# EFR32BG24_PartB.net
KiCad netlist of a schematic drawn in Altium Designer
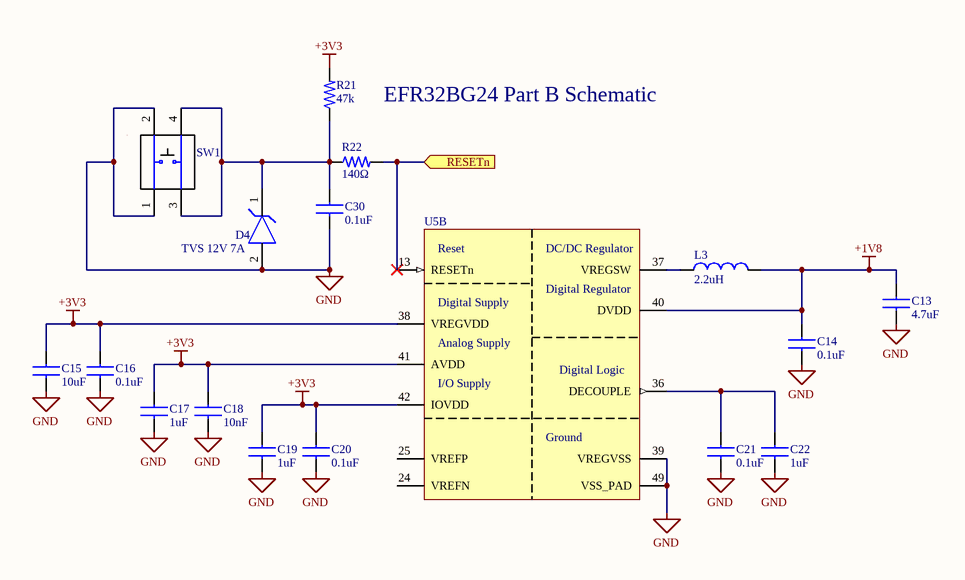
[diagram p0: EFR32BG24_PartB.SchDoc]

(export (version "E")
  (design (tool "Eeschema 10.0.6"))
  (components
    (comp (ref "C13")
      (value "4.7uF")
      (footprint "C_0603")
      (description "CAP CER 4.7UF 10V X5R 0603")
      (fields
        (field (name "MANUFACTURER") "Murata")
        (field (name "MANUFACTURER PART NUMBER") "GRM188R61A475KAAJD")
      )
      (libsource (lib "LPEDT_Parts") (part "C_4.7U_0603"))
    )
    (comp (ref "C14")
      (value "0.1uF")
      (footprint "C_0603")
      (description "CAP CER 0.1UF 10V X5R 0603")
      (fields
        (field (name "MANUFACTURER") "KEMET")
        (field (name "MANUFACTURER PART NUMBER") "C0603C104K8PAC7867")
      )
      (libsource (lib "LPEDT_Parts") (part "C_0.1U_0603"))
    )
    (comp (ref "C15")
      (value "10uF")
      (footprint "C_0603")
      (description "CAP CER 10UF 10V X5R 0603")
      (fields
        (field (name "MANUFACTURER") "Murata")
        (field (name "MANUFACTURER PART NUMBER") "GRM188R61A106ME69D")
      )
      (libsource (lib "LPEDT_Parts") (part "C_10U_0603"))
    )
    (comp (ref "C16")
      (value "0.1uF")
      (footprint "C_0603")
      (description "CAP CER 0.1UF 10V X5R 0603")
      (fields
        (field (name "MANUFACTURER") "KEMET")
        (field (name "MANUFACTURER PART NUMBER") "C0603C104K8PAC7867")
      )
      (libsource (lib "LPEDT_Parts") (part "C_0.1U_0603"))
    )
    (comp (ref "C17")
      (value "1uF")
      (footprint "C_0603")
      (description "CAP CER 1UF 10V X5R 0603")
      (fields
        (field (name "MANUFACTURER") "Murata")
        (field (name "MANUFACTURER PART NUMBER") "GRM188R61A105KA61D")
      )
      (libsource (lib "LPEDT_Parts") (part "C_1U_0603"))
    )
    (comp (ref "C18")
      (value "10nF")
      (footprint "C_0603")
      (fields
        (field (name "MANUFACTURER") "Murata")
        (field (name "MANUFACTURER PART NUMBER") "GCM188R72A103KA37D")
      )
      (libsource (lib "LPEDT_Parts") (part "C_10N_0603"))
    )
    (comp (ref "C19")
      (value "1uF")
      (footprint "C_0603")
      (description "CAP CER 1UF 10V X5R 0603")
      (fields
        (field (name "MANUFACTURER") "Murata")
        (field (name "MANUFACTURER PART NUMBER") "GRM188R61A105KA61D")
      )
      (libsource (lib "LPEDT_Parts") (part "C_1U_0603"))
    )
    (comp (ref "C20")
      (value "0.1uF")
      (footprint "C_0603")
      (description "CAP CER 0.1UF 10V X5R 0603")
      (fields
        (field (name "MANUFACTURER") "KEMET")
        (field (name "MANUFACTURER PART NUMBER") "C0603C104K8PAC7867")
      )
      (libsource (lib "LPEDT_Parts") (part "C_0.1U_0603"))
    )
    (comp (ref "C21")
      (value "0.1uF")
      (footprint "C_0603")
      (description "CAP CER 0.1UF 10V X5R 0603")
      (fields
        (field (name "MANUFACTURER") "KEMET")
        (field (name "MANUFACTURER PART NUMBER") "C0603C104K8PAC7867")
      )
      (libsource (lib "LPEDT_Parts") (part "C_0.1U_0603"))
    )
    (comp (ref "C22")
      (value "1uF")
      (footprint "C_0603")
      (description "CAP CER 1UF 10V X5R 0603")
      (fields
        (field (name "MANUFACTURER") "Murata")
        (field (name "MANUFACTURER PART NUMBER") "GRM188R61A105KA61D")
      )
      (libsource (lib "LPEDT_Parts") (part "C_1U_0603"))
    )
    (comp (ref "C30")
      (value "0.1uF")
      (footprint "C_0603")
      (description "CAP CER 0.1UF 10V X5R 0603")
      (fields
        (field (name "MANUFACTURER") "KEMET")
        (field (name "MANUFACTURER PART NUMBER") "C0603C104K8PAC7867")
      )
      (libsource (lib "LPEDT_Parts") (part "C_0.1U_0603"))
    )
    (comp (ref "D4")
      (value "TVS 12V 7A")
      (footprint "D_TVS")
      (description "TVS DIODE 5VWM 12VC SOD723")
      (fields
        (field (name "MANUFACTURER") "Littelfuse")
        (field (name "MANUFACTURER PART NUMBER") "SP1003-01DTG")
      )
      (libsource (lib "LPEDT_Parts") (part "D_TVS_7A"))
    )
    (comp (ref "L3")
      (value "2.2uH")
      (footprint "L_2828x30")
      (description "General Purpose Inductor, 2.2uH, 20%, 1 Element, Ferrite-Core, SMD, 1111")
      (fields
        (field (name "MANUFACTURER") "Wurth Electronics")
        (field (name "MANUFACTURER PART NUMBER") "744025002")
      )
      (libsource (lib "LPEDT_Parts") (part "L_2U2_2828"))
    )
    (comp (ref "R21")
      (value "47k")
      (footprint "R_0603")
      (fields
        (field (name "MANUFACTURER") "Yageo")
        (field (name "MANUFACTURER PART NUMBER") "RC0603FR-0747KL")
        (field (name "TOLERANCE") "1%")
      )
      (libsource (lib "LPEDT_Parts") (part "R_47K_0603"))
    )
    (comp (ref "R22")
      (value "140Ω")
      (footprint "R_0603")
      (description "RES 140OHM 0.1w 0603")
      (fields
        (field (name "MANUFACTURER") "Yageo")
        (field (name "MANUFACTURER PART NUMBER") "RC0603FR-07140RL")
      )
      (libsource (lib "LPEDT_Parts") (part "R_140_0603"))
    )
    (comp (ref "SW1")
      (value "SW_TactilePushButton")
      (footprint "SW_Tactile")
      (description "6 x 6 mm, 4.3 ~ 17 mm Actuator Height, 100 ~ 260 gf, Through Hole, SPST, Tactile Switch")
      (fields
        (field (name "MANUFACTURER") "CUI Devices")
        (field (name "MANUFACTURER PART NUMBER") "TS02-66-60-BK-100-LCR-D")
      )
      (libsource (lib "LPEDT_Parts") (part "SW_TactilePushButton"))
    )
    (comp (ref "U5")
      (value "EFR32BG24B110F1536IM48-B")
      (footprint "U_48QFN_6x6_2")
      (description "BG24, 2.4 GHz, 1536kB Flash, 256kB RAM, +10 dBm, Secure Vault High, 20-bit ADC +125C, QFN48")
      (fields (field (name "MANUFACTURER") "Silicon Labs"))
      (libsource (lib "LPEDT_Parts") (part "EFR32BG24B110F1536IM48-B"))
    )
  )
  (nets
    (net (code "1") (name "+1V8") (class "Default")
      (node (ref "C13") (pin "1") (pinfunction "1_1") (pintype "passive"))
      (node (ref "C14") (pin "1") (pinfunction "1_1") (pintype "passive"))
      (node (ref "L3") (pin "2") (pinfunction "2_2") (pintype "passive"))
      (node (ref "U5") (pin "40") (pinfunction "DVDD_40") (pintype "power_in"))
    )
    (net (code "2") (name "+3V3") (class "Default")
      (node (ref "C15") (pin "1") (pinfunction "1_1") (pintype "passive"))
      (node (ref "C16") (pin "2") (pinfunction "2_2") (pintype "passive"))
      (node (ref "C17") (pin "2") (pinfunction "2_2") (pintype "passive"))
      (node (ref "C18") (pin "1") (pinfunction "1_1") (pintype "passive"))
      (node (ref "C19") (pin "2") (pinfunction "2_2") (pintype "passive"))
      (node (ref "C20") (pin "2") (pinfunction "2_2") (pintype "passive"))
      (node (ref "R21") (pin "2") (pinfunction "2_2") (pintype "passive"))
      (node (ref "U5") (pin "38") (pinfunction "VREGVDD_38") (pintype "power_in"))
      (node (ref "U5") (pin "41") (pinfunction "AVDD_41") (pintype "power_in"))
      (node (ref "U5") (pin "42") (pinfunction "IOVDD_42") (pintype "power_in"))
    )
    (net (code "3") (name "/RESETn") (class "Default")
      (node (ref "R22") (pin "2") (pinfunction "2_2") (pintype "passive"))
      (node (ref "U5") (pin "13") (pinfunction "RESETn_13") (pintype "input"))
    )
    (net (code "4") (name "GND") (class "Default")
      (node (ref "C13") (pin "2") (pinfunction "2_2") (pintype "passive"))
      (node (ref "C14") (pin "2") (pinfunction "2_2") (pintype "passive"))
      (node (ref "C15") (pin "2") (pinfunction "2_2") (pintype "passive"))
      (node (ref "C16") (pin "1") (pinfunction "1_1") (pintype "passive"))
      (node (ref "C17") (pin "1") (pinfunction "1_1") (pintype "passive"))
      (node (ref "C18") (pin "2") (pinfunction "2_2") (pintype "passive"))
      (node (ref "C19") (pin "1") (pinfunction "1_1") (pintype "passive"))
      (node (ref "C20") (pin "1") (pinfunction "1_1") (pintype "passive"))
      (node (ref "C21") (pin "2") (pinfunction "2_2") (pintype "passive"))
      (node (ref "C22") (pin "2") (pinfunction "2_2") (pintype "passive"))
      (node (ref "C30") (pin "2") (pinfunction "2_2") (pintype "passive"))
      (node (ref "D4") (pin "2") (pinfunction "2_2") (pintype "passive"))
      (node (ref "SW1") (pin "1") (pinfunction "1_1") (pintype "passive"))
      (node (ref "SW1") (pin "2") (pinfunction "2_2") (pintype "passive"))
      (node (ref "U5") (pin "39") (pinfunction "VREGVSS_39") (pintype "power_in"))
      (node (ref "U5") (pin "49") (pinfunction "VSS_PAD_49") (pintype "power_in"))
    )
    (net (code "5") (name "Net-(C30-Pad1)") (class "Default")
      (node (ref "C30") (pin "1") (pinfunction "1_1") (pintype "passive"))
      (node (ref "D4") (pin "1") (pinfunction "1_1") (pintype "passive"))
      (node (ref "R21") (pin "1") (pinfunction "1_1") (pintype "passive"))
      (node (ref "R22") (pin "1") (pinfunction "1_1") (pintype "passive"))
      (node (ref "SW1") (pin "3") (pinfunction "3_3") (pintype "passive"))
      (node (ref "SW1") (pin "4") (pinfunction "4_4") (pintype "passive"))
    )
    (net (code "6") (name "Net-(U5B-DECOUPLE)") (class "Default")
      (node (ref "C21") (pin "1") (pinfunction "1_1") (pintype "passive"))
      (node (ref "C22") (pin "1") (pinfunction "1_1") (pintype "passive"))
      (node (ref "U5") (pin "36") (pinfunction "DECOUPLE_36") (pintype "output"))
    )
    (net (code "7") (name "Net-(U5B-VREGSW)") (class "Default")
      (node (ref "L3") (pin "1") (pinfunction "1_1") (pintype "passive"))
      (node (ref "U5") (pin "37") (pinfunction "VREGSW_37") (pintype "power_in"))
    )
    (net (code "8") (name "unconnected-(U5B-VREFN-Pad24)") (class "Default")
      (node (ref "U5") (pin "24") (pinfunction "VREFN_24") (pintype "power_in"))
    )
    (net (code "9") (name "unconnected-(U5B-VREFP-Pad25)") (class "Default")
      (node (ref "U5") (pin "25") (pinfunction "VREFP_25") (pintype "power_in"))
    )
  )
)
